# PCB_LT1711_LT1713.net
KiCad netlist of a schematic drawn in EAGLE
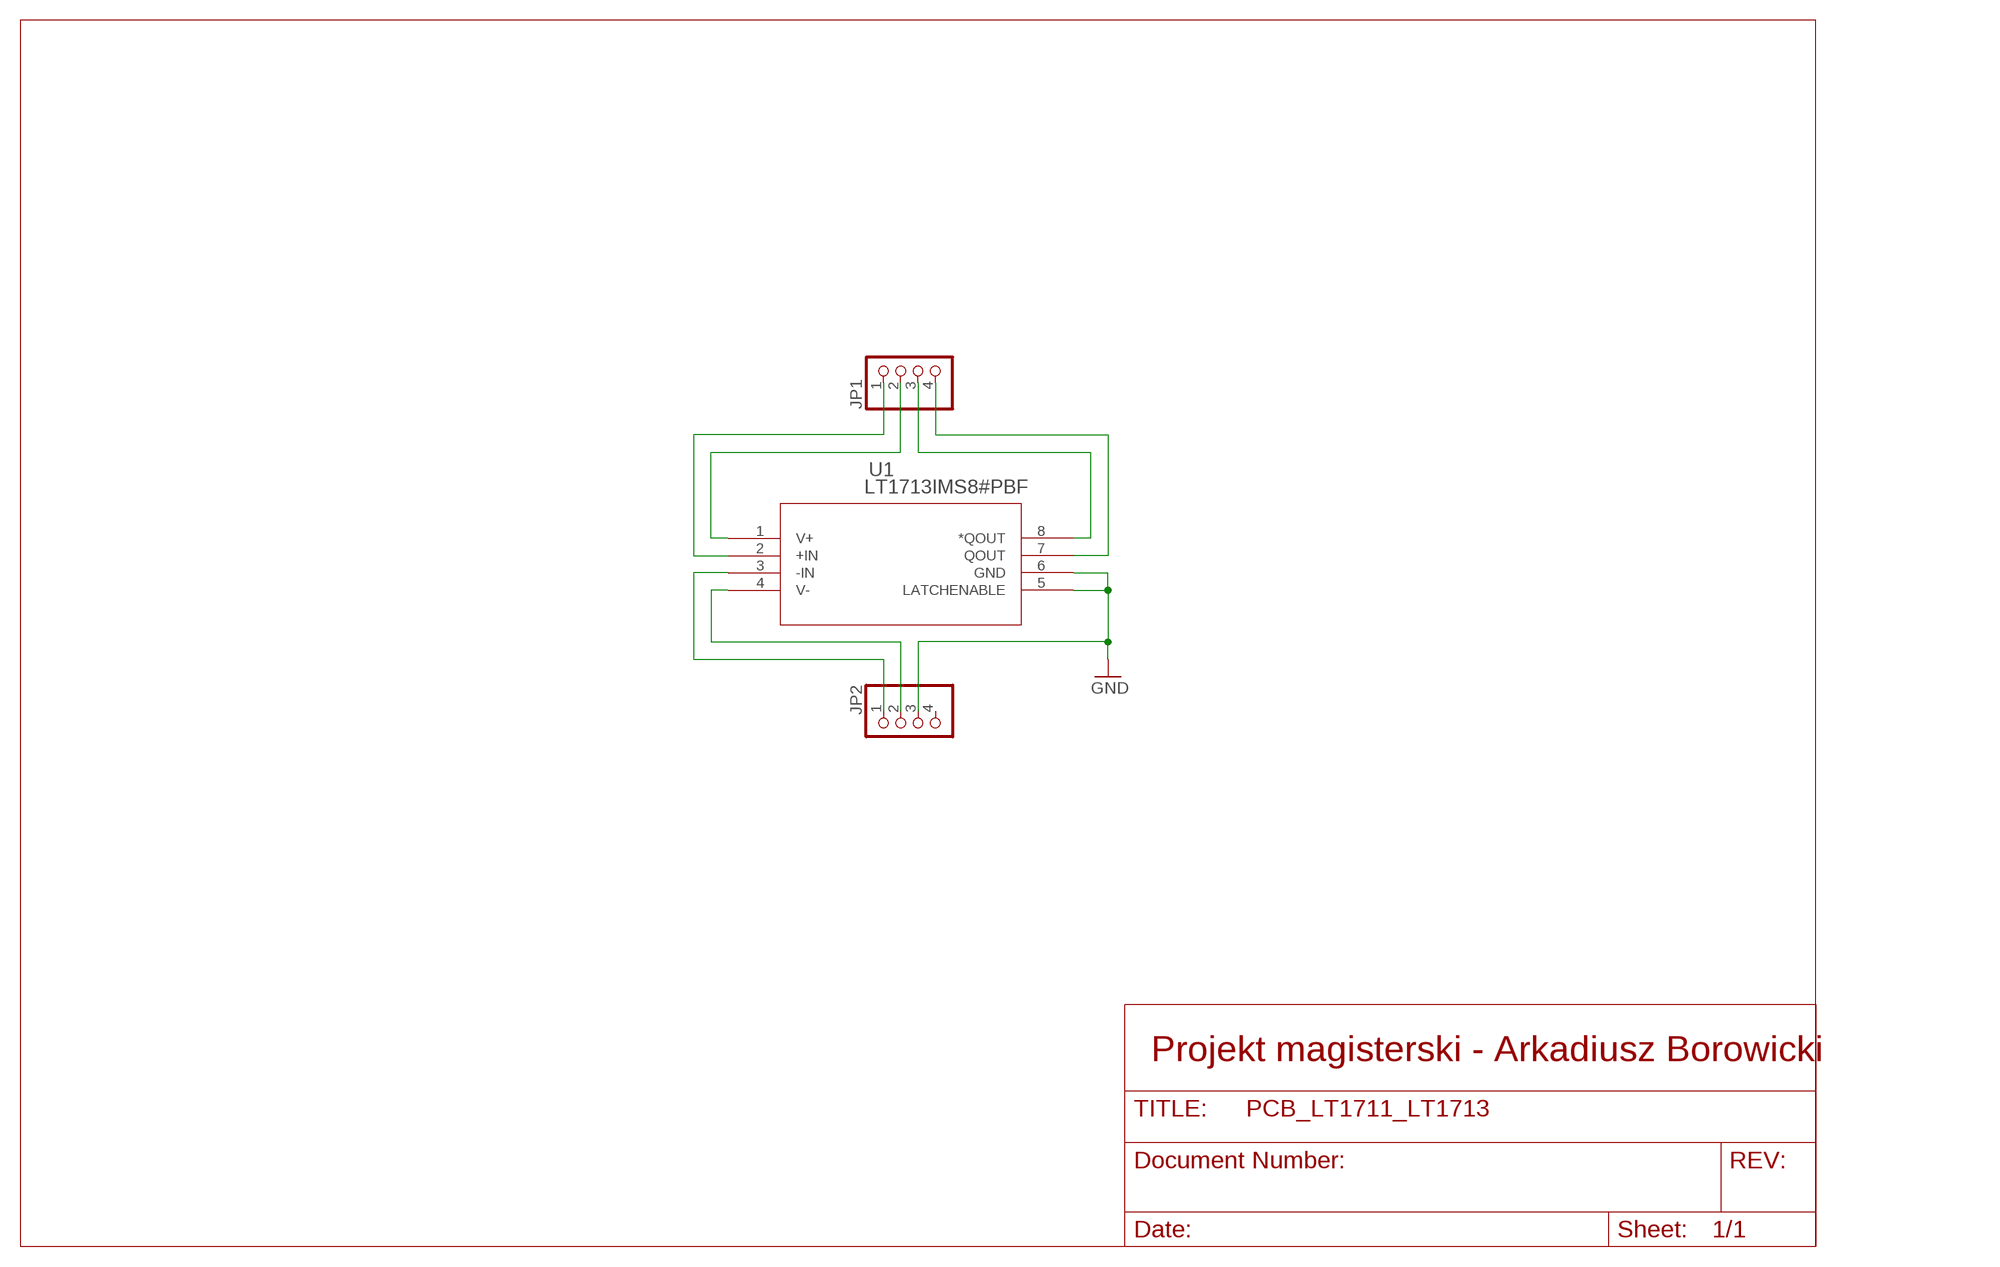
[diagram p0: schematic, sheet 1]

(export (version "E")
  (design (tool "Eeschema 10.0.6"))
  (components
    (comp (ref "JP1")
      (value "PINHD-1X4")
      (footprint "eagle-import:1X04")
      (libsource (lib "eagle-import") (part "PINHD-1X4"))
    )
    (comp (ref "JP2")
      (value "PINHD-1X4")
      (footprint "eagle-import:1X04")
      (libsource (lib "eagle-import") (part "PINHD-1X4"))
    )
    (comp (ref "U1")
      (value "LT1713IMS8#PBF")
      (footprint "eagle-import:MSOP-8_MS")
      (fields (field (name "MF") "Analog Devices"))
      (libsource (lib "eagle-import") (part "LT1713IMS8#PBF"))
    )
  )
  (nets
    (net (code "1") (name "GND") (class "Default")
      (node (ref "JP2") (pin "3") (pinfunction "3_3") (pintype "passive"))
      (node (ref "U1") (pin "5") (pinfunction "LATCHENABLE_5") (pintype "input"))
      (node (ref "U1") (pin "6") (pinfunction "GND_6") (pintype "power_in"))
    )
    (net (code "2") (name "Net-(U1-*QOUT)") (class "Default")
      (node (ref "JP1") (pin "3") (pinfunction "3_3") (pintype "passive"))
      (node (ref "U1") (pin "8") (pinfunction "*QOUT_8") (pintype "output"))
    )
    (net (code "3") (name "Net-(U1-+IN)") (class "Default")
      (node (ref "JP1") (pin "1") (pinfunction "1_1") (pintype "passive"))
      (node (ref "U1") (pin "2") (pinfunction "+IN_2") (pintype "input"))
    )
    (net (code "4") (name "Net-(U1--IN)") (class "Default")
      (node (ref "JP2") (pin "1") (pinfunction "1_1") (pintype "passive"))
      (node (ref "U1") (pin "3") (pinfunction "-IN_3") (pintype "input"))
    )
    (net (code "5") (name "Net-(U1-QOUT)") (class "Default")
      (node (ref "JP1") (pin "4") (pinfunction "4_4") (pintype "passive"))
      (node (ref "U1") (pin "7") (pinfunction "QOUT_7") (pintype "output"))
    )
    (net (code "6") (name "Net-(U1-V+)") (class "Default")
      (node (ref "JP1") (pin "2") (pinfunction "2_2") (pintype "passive"))
      (node (ref "U1") (pin "1") (pinfunction "V+_1") (pintype "power_in"))
    )
    (net (code "7") (name "Net-(U1-V-)") (class "Default")
      (node (ref "JP2") (pin "2") (pinfunction "2_2") (pintype "passive"))
      (node (ref "U1") (pin "4") (pinfunction "V-_4") (pintype "power_in"))
    )
    (net (code "8") (name "unconnected-(JP2-Pad4)") (class "Default")
      (node (ref "JP2") (pin "4") (pinfunction "4_4") (pintype "passive"))
    )
  )
)
